# eib-128.net
KiCad netlist of a schematic drawn in EAGLE
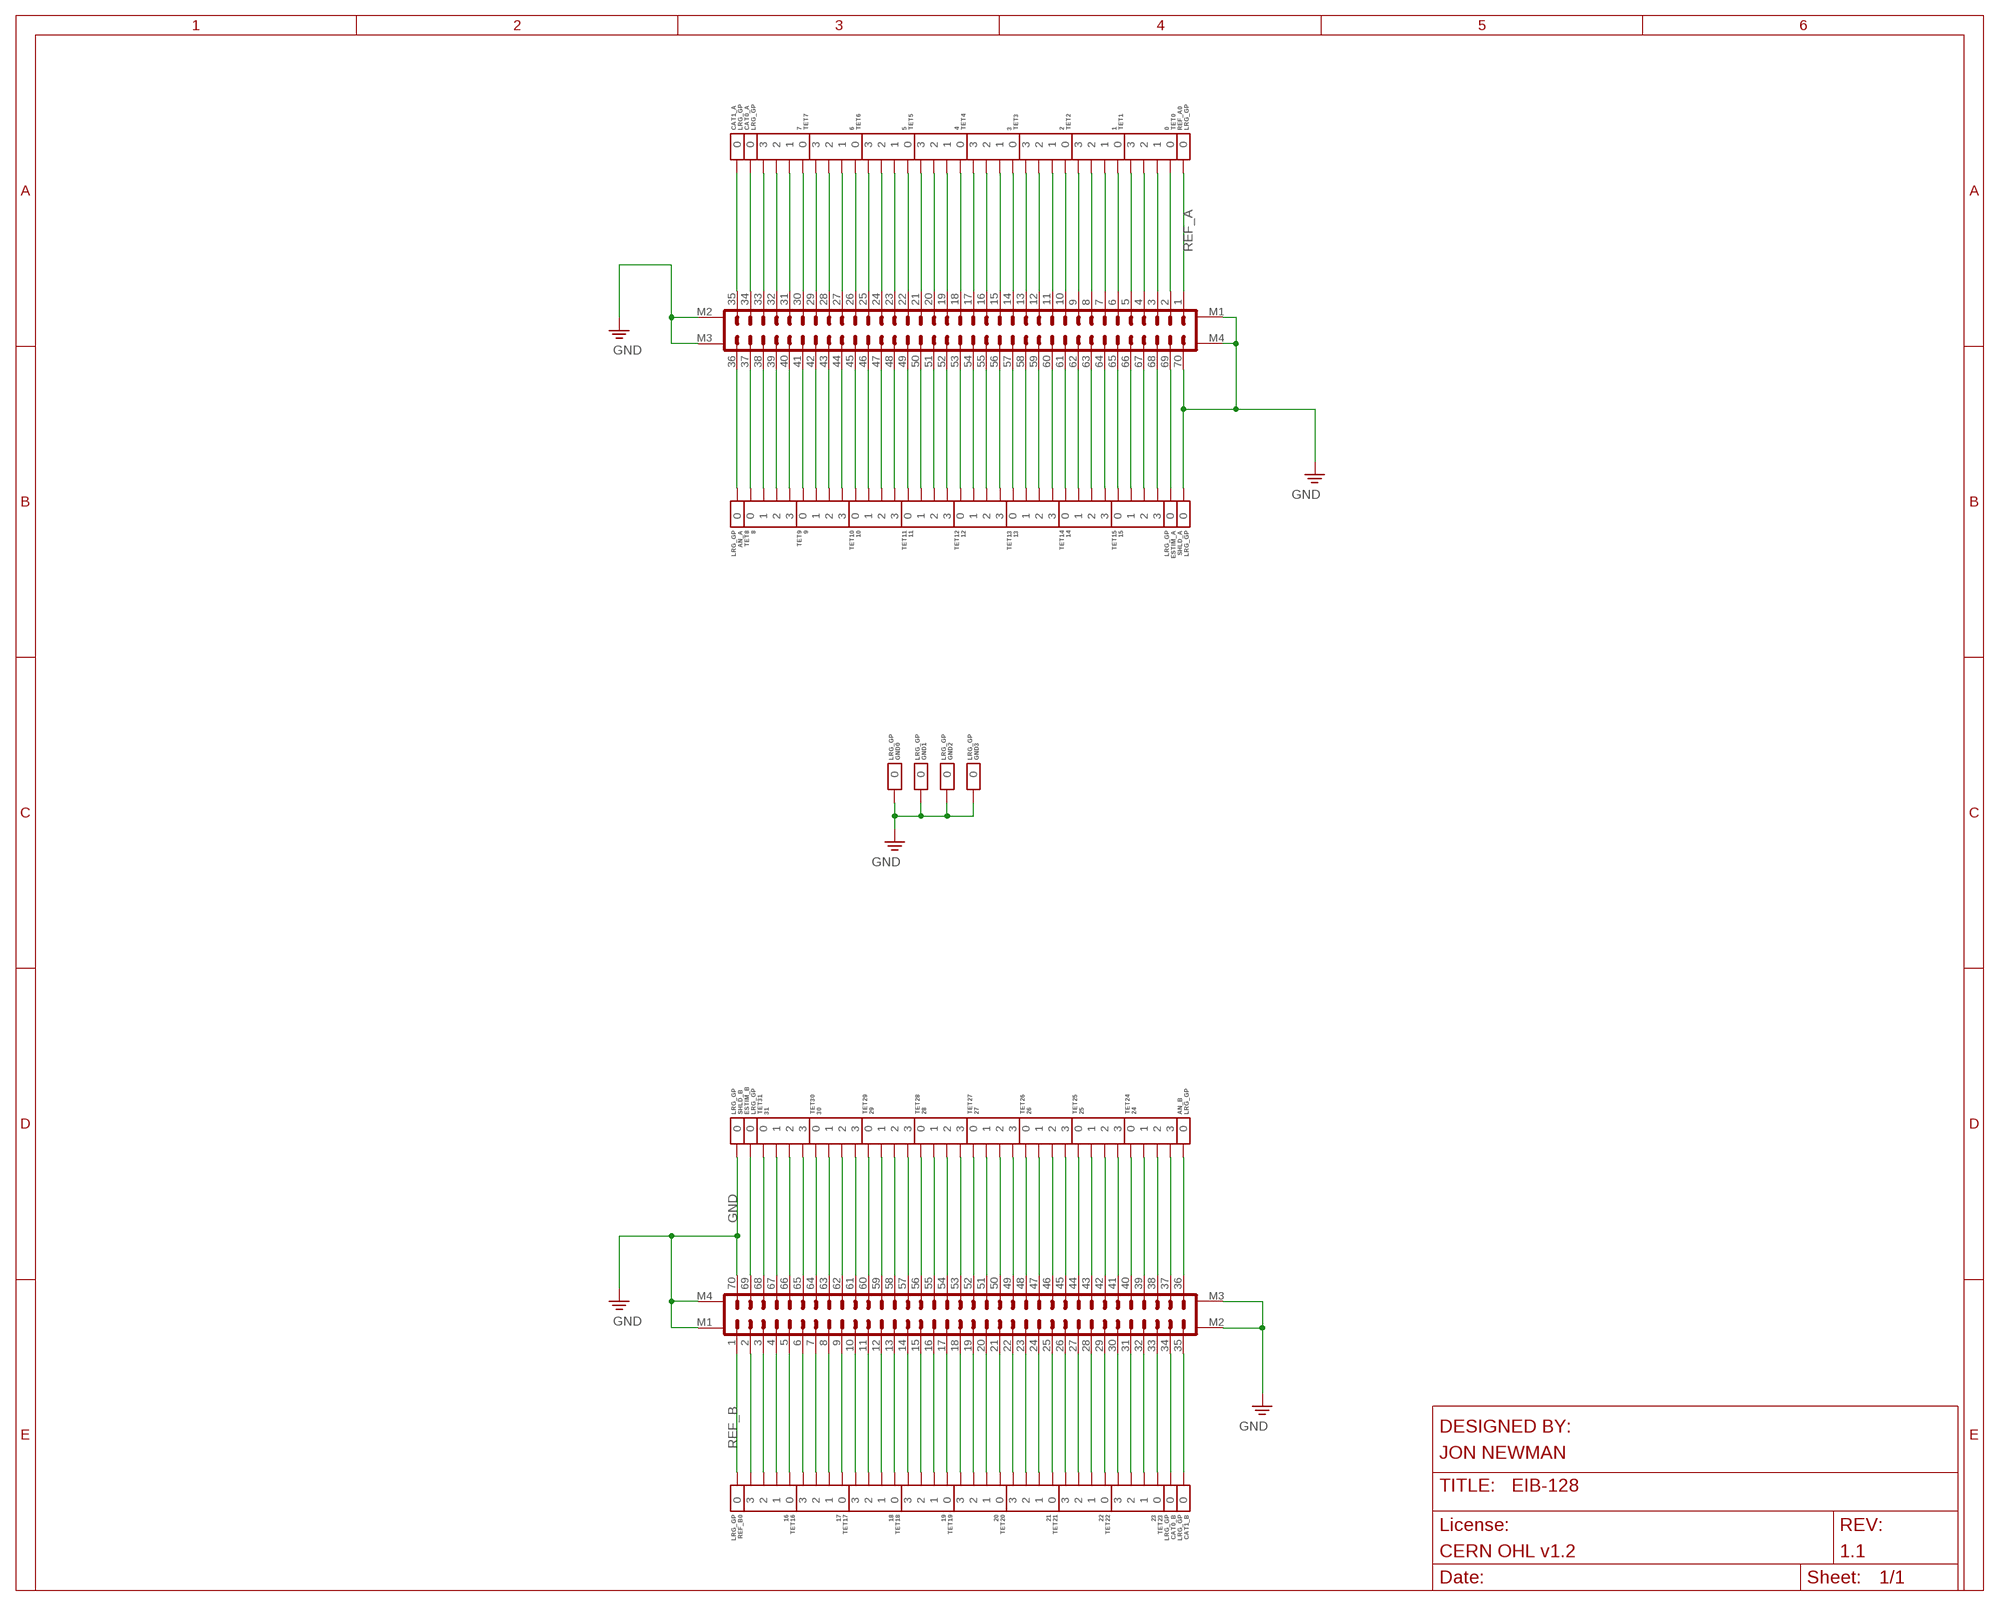
[diagram p0: schematic, sheet 1]

(export (version "E")
  (design (tool "Eeschema 10.0.6"))
  (components
    (comp (ref "A")
      (value "DF40HEAD")
      (footprint "eagle-import:DF40-70HEAD")
      (libsource (lib "eagle-import") (part "PINHD-2X35+4_DF40-70HEAD"))
    )
    (comp (ref "AN_A")
      (value "LRG_GP")
      (footprint "eagle-import:GOLDPIN_0.5ID_0.7OD")
      (libsource (lib "eagle-import") (part "GOLDPIN_0.5ID_0.7OD"))
    )
    (comp (ref "AN_B")
      (value "LRG_GP")
      (footprint "eagle-import:GOLDPIN_0.5ID_0.7OD")
      (libsource (lib "eagle-import") (part "GOLDPIN_0.5ID_0.7OD"))
    )
    (comp (ref "B")
      (value "DF40HEAD")
      (footprint "eagle-import:DF40-70HEAD")
      (libsource (lib "eagle-import") (part "PINHD-2X35+4_DF40-70HEAD"))
    )
    (comp (ref "CAT0_A")
      (value "LRG_GP")
      (footprint "eagle-import:GOLDPIN_0.5ID_0.7OD")
      (libsource (lib "eagle-import") (part "GOLDPIN_0.5ID_0.7OD"))
    )
    (comp (ref "CAT0_B")
      (value "LRG_GP")
      (footprint "eagle-import:GOLDPIN_0.5ID_0.7OD")
      (libsource (lib "eagle-import") (part "GOLDPIN_0.5ID_0.7OD"))
    )
    (comp (ref "CAT1_A")
      (value "LRG_GP")
      (footprint "eagle-import:GOLDPIN_0.5ID_0.7OD")
      (libsource (lib "eagle-import") (part "GOLDPIN_0.5ID_0.7OD"))
    )
    (comp (ref "CAT1_B")
      (value "LRG_GP")
      (footprint "eagle-import:GOLDPIN_0.5ID_0.7OD")
      (libsource (lib "eagle-import") (part "GOLDPIN_0.5ID_0.7OD"))
    )
    (comp (ref "ESTIM_A")
      (value "LRG_GP")
      (footprint "eagle-import:GOLDPIN_0.5ID_0.7OD")
      (libsource (lib "eagle-import") (part "GOLDPIN_0.5ID_0.7OD"))
    )
    (comp (ref "ESTIM_B")
      (value "LRG_GP")
      (footprint "eagle-import:GOLDPIN_0.5ID_0.7OD")
      (libsource (lib "eagle-import") (part "GOLDPIN_0.5ID_0.7OD"))
    )
    (comp (ref "GND0")
      (value "LRG_GP")
      (footprint "eagle-import:GOLDPIN_0.5ID_0.7OD")
      (libsource (lib "eagle-import") (part "GOLDPIN_0.5ID_0.7OD"))
    )
    (comp (ref "GND1")
      (value "LRG_GP")
      (footprint "eagle-import:GOLDPIN_0.5ID_0.7OD")
      (libsource (lib "eagle-import") (part "GOLDPIN_0.5ID_0.7OD"))
    )
    (comp (ref "GND2")
      (value "LRG_GP")
      (footprint "eagle-import:GOLDPIN_0.5ID_0.7OD")
      (libsource (lib "eagle-import") (part "GOLDPIN_0.5ID_0.7OD"))
    )
    (comp (ref "GND3")
      (value "LRG_GP")
      (footprint "eagle-import:GOLDPIN_0.5ID_0.7OD")
      (libsource (lib "eagle-import") (part "GOLDPIN_0.5ID_0.7OD"))
    )
    (comp (ref "REF_A0")
      (value "LRG_GP")
      (footprint "eagle-import:GOLDPIN_0.5ID_0.7OD")
      (libsource (lib "eagle-import") (part "GOLDPIN_0.5ID_0.7OD"))
    )
    (comp (ref "REF_B0")
      (value "LRG_GP")
      (footprint "eagle-import:GOLDPIN_0.5ID_0.7OD")
      (libsource (lib "eagle-import") (part "GOLDPIN_0.5ID_0.7OD"))
    )
    (comp (ref "SHLD_A")
      (value "LRG_GP")
      (footprint "eagle-import:GOLDPIN_0.5ID_0.7OD")
      (libsource (lib "eagle-import") (part "GOLDPIN_0.5ID_0.7OD"))
    )
    (comp (ref "SHLD_B")
      (value "LRG_GP")
      (footprint "eagle-import:GOLDPIN_0.5ID_0.7OD")
      (libsource (lib "eagle-import") (part "GOLDPIN_0.5ID_0.7OD"))
    )
    (comp (ref "TET0")
      (value "0")
      (footprint "eagle-import:TETRODE_128_0.5ID_0.7OD")
      (libsource (lib "eagle-import") (part "TETRODE_128_0.5ID_0.7OD"))
    )
    (comp (ref "TET1")
      (value "1")
      (footprint "eagle-import:TETRODE_128_0.5ID_0.7OD")
      (libsource (lib "eagle-import") (part "TETRODE_128_0.5ID_0.7OD"))
    )
    (comp (ref "TET2")
      (value "2")
      (footprint "eagle-import:TETRODE_128_0.5ID_0.7OD")
      (libsource (lib "eagle-import") (part "TETRODE_128_0.5ID_0.7OD"))
    )
    (comp (ref "TET3")
      (value "3")
      (footprint "eagle-import:TETRODE_128_0.5ID_0.7OD")
      (libsource (lib "eagle-import") (part "TETRODE_128_0.5ID_0.7OD"))
    )
    (comp (ref "TET4")
      (value "4")
      (footprint "eagle-import:TETRODE_128_0.5ID_0.7OD")
      (libsource (lib "eagle-import") (part "TETRODE_128_0.5ID_0.7OD"))
    )
    (comp (ref "TET5")
      (value "5")
      (footprint "eagle-import:TETRODE_128_0.5ID_0.7OD")
      (libsource (lib "eagle-import") (part "TETRODE_128_0.5ID_0.7OD"))
    )
    (comp (ref "TET6")
      (value "6")
      (footprint "eagle-import:TETRODE_128_0.5ID_0.7OD")
      (libsource (lib "eagle-import") (part "TETRODE_128_0.5ID_0.7OD"))
    )
    (comp (ref "TET7")
      (value "7")
      (footprint "eagle-import:TETRODE_128_0.5ID_0.7OD")
      (libsource (lib "eagle-import") (part "TETRODE_128_0.5ID_0.7OD"))
    )
    (comp (ref "TET8")
      (value "8")
      (footprint "eagle-import:TETRODE_128_0.5ID_0.7OD")
      (libsource (lib "eagle-import") (part "TETRODE_128_0.5ID_0.7OD"))
    )
    (comp (ref "TET9")
      (value "9")
      (footprint "eagle-import:TETRODE_128_0.5ID_0.7OD")
      (libsource (lib "eagle-import") (part "TETRODE_128_0.5ID_0.7OD"))
    )
    (comp (ref "TET10")
      (value "10")
      (footprint "eagle-import:TETRODE_128_0.5ID_0.7OD")
      (libsource (lib "eagle-import") (part "TETRODE_128_0.5ID_0.7OD"))
    )
    (comp (ref "TET11")
      (value "11")
      (footprint "eagle-import:TETRODE_128_0.5ID_0.7OD")
      (libsource (lib "eagle-import") (part "TETRODE_128_0.5ID_0.7OD"))
    )
    (comp (ref "TET12")
      (value "12")
      (footprint "eagle-import:TETRODE_128_0.5ID_0.7OD")
      (libsource (lib "eagle-import") (part "TETRODE_128_0.5ID_0.7OD"))
    )
    (comp (ref "TET13")
      (value "13")
      (footprint "eagle-import:TETRODE_128_0.5ID_0.7OD")
      (libsource (lib "eagle-import") (part "TETRODE_128_0.5ID_0.7OD"))
    )
    (comp (ref "TET14")
      (value "14")
      (footprint "eagle-import:TETRODE_128_0.5ID_0.7OD")
      (libsource (lib "eagle-import") (part "TETRODE_128_0.5ID_0.7OD"))
    )
    (comp (ref "TET15")
      (value "15")
      (footprint "eagle-import:TETRODE_128_0.5ID_0.7OD")
      (libsource (lib "eagle-import") (part "TETRODE_128_0.5ID_0.7OD"))
    )
    (comp (ref "TET16")
      (value "16")
      (footprint "eagle-import:TETRODE_128_0.5ID_0.7OD")
      (libsource (lib "eagle-import") (part "TETRODE_128_0.5ID_0.7OD"))
    )
    (comp (ref "TET17")
      (value "17")
      (footprint "eagle-import:TETRODE_128_0.5ID_0.7OD")
      (libsource (lib "eagle-import") (part "TETRODE_128_0.5ID_0.7OD"))
    )
    (comp (ref "TET18")
      (value "18")
      (footprint "eagle-import:TETRODE_128_0.5ID_0.7OD")
      (libsource (lib "eagle-import") (part "TETRODE_128_0.5ID_0.7OD"))
    )
    (comp (ref "TET19")
      (value "19")
      (footprint "eagle-import:TETRODE_128_0.5ID_0.7OD")
      (libsource (lib "eagle-import") (part "TETRODE_128_0.5ID_0.7OD"))
    )
    (comp (ref "TET20")
      (value "20")
      (footprint "eagle-import:TETRODE_128_0.5ID_0.7OD")
      (libsource (lib "eagle-import") (part "TETRODE_128_0.5ID_0.7OD"))
    )
    (comp (ref "TET21")
      (value "21")
      (footprint "eagle-import:TETRODE_128_0.5ID_0.7OD")
      (libsource (lib "eagle-import") (part "TETRODE_128_0.5ID_0.7OD"))
    )
    (comp (ref "TET22")
      (value "22")
      (footprint "eagle-import:TETRODE_128_0.5ID_0.7OD")
      (libsource (lib "eagle-import") (part "TETRODE_128_0.5ID_0.7OD"))
    )
    (comp (ref "TET23")
      (value "23")
      (footprint "eagle-import:TETRODE_128_0.5ID_0.7OD")
      (libsource (lib "eagle-import") (part "TETRODE_128_0.5ID_0.7OD"))
    )
    (comp (ref "TET24")
      (value "24")
      (footprint "eagle-import:TETRODE_128_0.5ID_0.7OD")
      (libsource (lib "eagle-import") (part "TETRODE_128_0.5ID_0.7OD"))
    )
    (comp (ref "TET25")
      (value "25")
      (footprint "eagle-import:TETRODE_128_0.5ID_0.7OD")
      (libsource (lib "eagle-import") (part "TETRODE_128_0.5ID_0.7OD"))
    )
    (comp (ref "TET26")
      (value "26")
      (footprint "eagle-import:TETRODE_128_0.5ID_0.7OD")
      (libsource (lib "eagle-import") (part "TETRODE_128_0.5ID_0.7OD"))
    )
    (comp (ref "TET27")
      (value "27")
      (footprint "eagle-import:TETRODE_128_0.5ID_0.7OD")
      (libsource (lib "eagle-import") (part "TETRODE_128_0.5ID_0.7OD"))
    )
    (comp (ref "TET28")
      (value "28")
      (footprint "eagle-import:TETRODE_128_0.5ID_0.7OD")
      (libsource (lib "eagle-import") (part "TETRODE_128_0.5ID_0.7OD"))
    )
    (comp (ref "TET29")
      (value "29")
      (footprint "eagle-import:TETRODE_128_0.5ID_0.7OD")
      (libsource (lib "eagle-import") (part "TETRODE_128_0.5ID_0.7OD"))
    )
    (comp (ref "TET30")
      (value "30")
      (footprint "eagle-import:TETRODE_128_0.5ID_0.7OD")
      (libsource (lib "eagle-import") (part "TETRODE_128_0.5ID_0.7OD"))
    )
    (comp (ref "TET31")
      (value "31")
      (footprint "eagle-import:TETRODE_128_0.5ID_0.7OD")
      (libsource (lib "eagle-import") (part "TETRODE_128_0.5ID_0.7OD"))
    )
  )
  (nets
    (net (code "1") (name "/REF_A") (class "Default")
      (node (ref "A") (pin "1") (pinfunction "1_1") (pintype "bidirectional"))
      (node (ref "REF_A0") (pin "P$1") (pinfunction "0_P$1") (pintype "bidirectional"))
    )
    (net (code "2") (name "/REF_B") (class "Default")
      (node (ref "B") (pin "1") (pinfunction "1_1") (pintype "bidirectional"))
      (node (ref "REF_B0") (pin "P$1") (pinfunction "0_P$1") (pintype "bidirectional"))
    )
    (net (code "3") (name "GND") (class "Default")
      (node (ref "A") (pin "70") (pinfunction "70_70") (pintype "bidirectional"))
      (node (ref "A") (pin "M1") (pinfunction "M1_M1") (pintype "bidirectional"))
      (node (ref "A") (pin "M2") (pinfunction "M2_M2") (pintype "bidirectional"))
      (node (ref "A") (pin "M3") (pinfunction "M3_M3") (pintype "bidirectional"))
      (node (ref "A") (pin "M4") (pinfunction "M4_M4") (pintype "bidirectional"))
      (node (ref "B") (pin "70") (pinfunction "70_70") (pintype "bidirectional"))
      (node (ref "B") (pin "M1") (pinfunction "M1_M1") (pintype "bidirectional"))
      (node (ref "B") (pin "M2") (pinfunction "M2_M2") (pintype "bidirectional"))
      (node (ref "B") (pin "M3") (pinfunction "M3_M3") (pintype "bidirectional"))
      (node (ref "B") (pin "M4") (pinfunction "M4_M4") (pintype "bidirectional"))
      (node (ref "GND0") (pin "P$1") (pinfunction "0_P$1") (pintype "bidirectional"))
      (node (ref "GND1") (pin "P$1") (pinfunction "0_P$1") (pintype "bidirectional"))
      (node (ref "GND2") (pin "P$1") (pinfunction "0_P$1") (pintype "bidirectional"))
      (node (ref "GND3") (pin "P$1") (pinfunction "0_P$1") (pintype "bidirectional"))
      (node (ref "SHLD_A") (pin "P$1") (pinfunction "0_P$1") (pintype "bidirectional"))
      (node (ref "SHLD_B") (pin "P$1") (pinfunction "0_P$1") (pintype "bidirectional"))
    )
    (net (code "4") (name "Net-(A-Pad2)") (class "Default")
      (node (ref "A") (pin "2") (pinfunction "2_2") (pintype "bidirectional"))
      (node (ref "TET0") (pin "0") (pinfunction "0_0") (pintype "bidirectional"))
    )
    (net (code "5") (name "Net-(A-Pad3)") (class "Default")
      (node (ref "A") (pin "3") (pinfunction "3_3") (pintype "bidirectional"))
      (node (ref "TET0") (pin "1") (pinfunction "1_1") (pintype "bidirectional"))
    )
    (net (code "6") (name "Net-(A-Pad4)") (class "Default")
      (node (ref "A") (pin "4") (pinfunction "4_4") (pintype "bidirectional"))
      (node (ref "TET0") (pin "2") (pinfunction "2_2") (pintype "bidirectional"))
    )
    (net (code "7") (name "Net-(A-Pad5)") (class "Default")
      (node (ref "A") (pin "5") (pinfunction "5_5") (pintype "bidirectional"))
      (node (ref "TET0") (pin "3") (pinfunction "3_3") (pintype "bidirectional"))
    )
    (net (code "8") (name "Net-(A-Pad6)") (class "Default")
      (node (ref "A") (pin "6") (pinfunction "6_6") (pintype "bidirectional"))
      (node (ref "TET1") (pin "0") (pinfunction "0_0") (pintype "bidirectional"))
    )
    (net (code "9") (name "Net-(A-Pad7)") (class "Default")
      (node (ref "A") (pin "7") (pinfunction "7_7") (pintype "bidirectional"))
      (node (ref "TET1") (pin "1") (pinfunction "1_1") (pintype "bidirectional"))
    )
    (net (code "10") (name "Net-(A-Pad8)") (class "Default")
      (node (ref "A") (pin "8") (pinfunction "8_8") (pintype "bidirectional"))
      (node (ref "TET1") (pin "2") (pinfunction "2_2") (pintype "bidirectional"))
    )
    (net (code "11") (name "Net-(A-Pad9)") (class "Default")
      (node (ref "A") (pin "9") (pinfunction "9_9") (pintype "bidirectional"))
      (node (ref "TET1") (pin "3") (pinfunction "3_3") (pintype "bidirectional"))
    )
    (net (code "12") (name "Net-(A-Pad10)") (class "Default")
      (node (ref "A") (pin "10") (pinfunction "10_10") (pintype "bidirectional"))
      (node (ref "TET2") (pin "0") (pinfunction "0_0") (pintype "bidirectional"))
    )
    (net (code "13") (name "Net-(A-Pad11)") (class "Default")
      (node (ref "A") (pin "11") (pinfunction "11_11") (pintype "bidirectional"))
      (node (ref "TET2") (pin "1") (pinfunction "1_1") (pintype "bidirectional"))
    )
    (net (code "14") (name "Net-(A-Pad12)") (class "Default")
      (node (ref "A") (pin "12") (pinfunction "12_12") (pintype "bidirectional"))
      (node (ref "TET2") (pin "2") (pinfunction "2_2") (pintype "bidirectional"))
    )
    (net (code "15") (name "Net-(A-Pad13)") (class "Default")
      (node (ref "A") (pin "13") (pinfunction "13_13") (pintype "bidirectional"))
      (node (ref "TET2") (pin "3") (pinfunction "3_3") (pintype "bidirectional"))
    )
    (net (code "16") (name "Net-(A-Pad14)") (class "Default")
      (node (ref "A") (pin "14") (pinfunction "14_14") (pintype "bidirectional"))
      (node (ref "TET3") (pin "0") (pinfunction "0_0") (pintype "bidirectional"))
    )
    (net (code "17") (name "Net-(A-Pad15)") (class "Default")
      (node (ref "A") (pin "15") (pinfunction "15_15") (pintype "bidirectional"))
      (node (ref "TET3") (pin "1") (pinfunction "1_1") (pintype "bidirectional"))
    )
    (net (code "18") (name "Net-(A-Pad16)") (class "Default")
      (node (ref "A") (pin "16") (pinfunction "16_16") (pintype "bidirectional"))
      (node (ref "TET3") (pin "2") (pinfunction "2_2") (pintype "bidirectional"))
    )
    (net (code "19") (name "Net-(A-Pad17)") (class "Default")
      (node (ref "A") (pin "17") (pinfunction "17_17") (pintype "bidirectional"))
      (node (ref "TET3") (pin "3") (pinfunction "3_3") (pintype "bidirectional"))
    )
    (net (code "20") (name "Net-(A-Pad18)") (class "Default")
      (node (ref "A") (pin "18") (pinfunction "18_18") (pintype "bidirectional"))
      (node (ref "TET4") (pin "0") (pinfunction "0_0") (pintype "bidirectional"))
    )
    (net (code "21") (name "Net-(A-Pad19)") (class "Default")
      (node (ref "A") (pin "19") (pinfunction "19_19") (pintype "bidirectional"))
      (node (ref "TET4") (pin "1") (pinfunction "1_1") (pintype "bidirectional"))
    )
    (net (code "22") (name "Net-(A-Pad20)") (class "Default")
      (node (ref "A") (pin "20") (pinfunction "20_20") (pintype "bidirectional"))
      (node (ref "TET4") (pin "2") (pinfunction "2_2") (pintype "bidirectional"))
    )
    (net (code "23") (name "Net-(A-Pad21)") (class "Default")
      (node (ref "A") (pin "21") (pinfunction "21_21") (pintype "bidirectional"))
      (node (ref "TET4") (pin "3") (pinfunction "3_3") (pintype "bidirectional"))
    )
    (net (code "24") (name "Net-(A-Pad22)") (class "Default")
      (node (ref "A") (pin "22") (pinfunction "22_22") (pintype "bidirectional"))
      (node (ref "TET5") (pin "0") (pinfunction "0_0") (pintype "bidirectional"))
    )
    (net (code "25") (name "Net-(A-Pad23)") (class "Default")
      (node (ref "A") (pin "23") (pinfunction "23_23") (pintype "bidirectional"))
      (node (ref "TET5") (pin "1") (pinfunction "1_1") (pintype "bidirectional"))
    )
    (net (code "26") (name "Net-(A-Pad24)") (class "Default")
      (node (ref "A") (pin "24") (pinfunction "24_24") (pintype "bidirectional"))
      (node (ref "TET5") (pin "2") (pinfunction "2_2") (pintype "bidirectional"))
    )
    (net (code "27") (name "Net-(A-Pad25)") (class "Default")
      (node (ref "A") (pin "25") (pinfunction "25_25") (pintype "bidirectional"))
      (node (ref "TET5") (pin "3") (pinfunction "3_3") (pintype "bidirectional"))
    )
    (net (code "28") (name "Net-(A-Pad26)") (class "Default")
      (node (ref "A") (pin "26") (pinfunction "26_26") (pintype "bidirectional"))
      (node (ref "TET6") (pin "0") (pinfunction "0_0") (pintype "bidirectional"))
    )
    (net (code "29") (name "Net-(A-Pad27)") (class "Default")
      (node (ref "A") (pin "27") (pinfunction "27_27") (pintype "bidirectional"))
      (node (ref "TET6") (pin "1") (pinfunction "1_1") (pintype "bidirectional"))
    )
    (net (code "30") (name "Net-(A-Pad28)") (class "Default")
      (node (ref "A") (pin "28") (pinfunction "28_28") (pintype "bidirectional"))
      (node (ref "TET6") (pin "2") (pinfunction "2_2") (pintype "bidirectional"))
    )
    (net (code "31") (name "Net-(A-Pad29)") (class "Default")
      (node (ref "A") (pin "29") (pinfunction "29_29") (pintype "bidirectional"))
      (node (ref "TET6") (pin "3") (pinfunction "3_3") (pintype "bidirectional"))
    )
    (net (code "32") (name "Net-(A-Pad30)") (class "Default")
      (node (ref "A") (pin "30") (pinfunction "30_30") (pintype "bidirectional"))
      (node (ref "TET7") (pin "0") (pinfunction "0_0") (pintype "bidirectional"))
    )
    (net (code "33") (name "Net-(A-Pad31)") (class "Default")
      (node (ref "A") (pin "31") (pinfunction "31_31") (pintype "bidirectional"))
      (node (ref "TET7") (pin "1") (pinfunction "1_1") (pintype "bidirectional"))
    )
    (net (code "34") (name "Net-(A-Pad32)") (class "Default")
      (node (ref "A") (pin "32") (pinfunction "32_32") (pintype "bidirectional"))
      (node (ref "TET7") (pin "2") (pinfunction "2_2") (pintype "bidirectional"))
    )
    (net (code "35") (name "Net-(A-Pad33)") (class "Default")
      (node (ref "A") (pin "33") (pinfunction "33_33") (pintype "bidirectional"))
      (node (ref "TET7") (pin "3") (pinfunction "3_3") (pintype "bidirectional"))
    )
    (net (code "36") (name "Net-(A-Pad37)") (class "Default")
      (node (ref "A") (pin "37") (pinfunction "37_37") (pintype "bidirectional"))
      (node (ref "TET8") (pin "0") (pinfunction "0_0") (pintype "bidirectional"))
    )
    (net (code "37") (name "Net-(A-Pad38)") (class "Default")
      (node (ref "A") (pin "38") (pinfunction "38_38") (pintype "bidirectional"))
      (node (ref "TET8") (pin "1") (pinfunction "1_1") (pintype "bidirectional"))
    )
    (net (code "38") (name "Net-(A-Pad39)") (class "Default")
      (node (ref "A") (pin "39") (pinfunction "39_39") (pintype "bidirectional"))
      (node (ref "TET8") (pin "2") (pinfunction "2_2") (pintype "bidirectional"))
    )
    (net (code "39") (name "Net-(A-Pad40)") (class "Default")
      (node (ref "A") (pin "40") (pinfunction "40_40") (pintype "bidirectional"))
      (node (ref "TET8") (pin "3") (pinfunction "3_3") (pintype "bidirectional"))
    )
    (net (code "40") (name "Net-(A-Pad41)") (class "Default")
      (node (ref "A") (pin "41") (pinfunction "41_41") (pintype "bidirectional"))
      (node (ref "TET9") (pin "0") (pinfunction "0_0") (pintype "bidirectional"))
    )
    (net (code "41") (name "Net-(A-Pad42)") (class "Default")
      (node (ref "A") (pin "42") (pinfunction "42_42") (pintype "bidirectional"))
      (node (ref "TET9") (pin "1") (pinfunction "1_1") (pintype "bidirectional"))
    )
    (net (code "42") (name "Net-(A-Pad43)") (class "Default")
      (node (ref "A") (pin "43") (pinfunction "43_43") (pintype "bidirectional"))
      (node (ref "TET9") (pin "2") (pinfunction "2_2") (pintype "bidirectional"))
    )
    (net (code "43") (name "Net-(A-Pad44)") (class "Default")
      (node (ref "A") (pin "44") (pinfunction "44_44") (pintype "bidirectional"))
      (node (ref "TET9") (pin "3") (pinfunction "3_3") (pintype "bidirectional"))
    )
    (net (code "44") (name "Net-(A-Pad45)") (class "Default")
      (node (ref "A") (pin "45") (pinfunction "45_45") (pintype "bidirectional"))
      (node (ref "TET10") (pin "0") (pinfunction "0_0") (pintype "bidirectional"))
    )
    (net (code "45") (name "Net-(A-Pad46)") (class "Default")
      (node (ref "A") (pin "46") (pinfunction "46_46") (pintype "bidirectional"))
      (node (ref "TET10") (pin "1") (pinfunction "1_1") (pintype "bidirectional"))
    )
    (net (code "46") (name "Net-(A-Pad47)") (class "Default")
      (node (ref "A") (pin "47") (pinfunction "47_47") (pintype "bidirectional"))
      (node (ref "TET10") (pin "2") (pinfunction "2_2") (pintype "bidirectional"))
    )
    (net (code "47") (name "Net-(A-Pad48)") (class "Default")
      (node (ref "A") (pin "48") (pinfunction "48_48") (pintype "bidirectional"))
      (node (ref "TET10") (pin "3") (pinfunction "3_3") (pintype "bidirectional"))
    )
    (net (code "48") (name "Net-(A-Pad49)") (class "Default")
      (node (ref "A") (pin "49") (pinfunction "49_49") (pintype "bidirectional"))
      (node (ref "TET11") (pin "0") (pinfunction "0_0") (pintype "bidirectional"))
    )
    (net (code "49") (name "Net-(A-Pad50)") (class "Default")
      (node (ref "A") (pin "50") (pinfunction "50_50") (pintype "bidirectional"))
      (node (ref "TET11") (pin "1") (pinfunction "1_1") (pintype "bidirectional"))
    )
    (net (code "50") (name "Net-(A-Pad51)") (class "Default")
      (node (ref "A") (pin "51") (pinfunction "51_51") (pintype "bidirectional"))
      (node (ref "TET11") (pin "2") (pinfunction "2_2") (pintype "bidirectional"))
    )
    (net (code "51") (name "Net-(A-Pad52)") (class "Default")
      (node (ref "A") (pin "52") (pinfunction "52_52") (pintype "bidirectional"))
      (node (ref "TET11") (pin "3") (pinfunction "3_3") (pintype "bidirectional"))
    )
    (net (code "52") (name "Net-(A-Pad53)") (class "Default")
      (node (ref "A") (pin "53") (pinfunction "53_53") (pintype "bidirectional"))
      (node (ref "TET12") (pin "0") (pinfunction "0_0") (pintype "bidirectional"))
    )
    (net (code "53") (name "Net-(A-Pad54)") (class "Default")
      (node (ref "A") (pin "54") (pinfunction "54_54") (pintype "bidirectional"))
      (node (ref "TET12") (pin "1") (pinfunction "1_1") (pintype "bidirectional"))
    )
    (net (code "54") (name "Net-(A-Pad55)") (class "Default")
      (node (ref "A") (pin "55") (pinfunction "55_55") (pintype "bidirectional"))
      (node (ref "TET12") (pin "2") (pinfunction "2_2") (pintype "bidirectional"))
    )
    (net (code "55") (name "Net-(A-Pad56)") (class "Default")
      (node (ref "A") (pin "56") (pinfunction "56_56") (pintype "bidirectional"))
      (node (ref "TET12") (pin "3") (pinfunction "3_3") (pintype "bidirectional"))
    )
    (net (code "56") (name "Net-(A-Pad57)") (class "Default")
      (node (ref "A") (pin "57") (pinfunction "57_57") (pintype "bidirectional"))
      (node (ref "TET13") (pin "0") (pinfunction "0_0") (pintype "bidirectional"))
    )
    (net (code "57") (name "Net-(A-Pad58)") (class "Default")
      (node (ref "A") (pin "58") (pinfunction "58_58") (pintype "bidirectional"))
      (node (ref "TET13") (pin "1") (pinfunction "1_1") (pintype "bidirectional"))
    )
    (net (code "58") (name "Net-(A-Pad59)") (class "Default")
      (node (ref "A") (pin "59") (pinfunction "59_59") (pintype "bidirectional"))
      (node (ref "TET13") (pin "2") (pinfunction "2_2") (pintype "bidirectional"))
    )
    (net (code "59") (name "Net-(A-Pad60)") (class "Default")
      (node (ref "A") (pin "60") (pinfunction "60_60") (pintype "bidirectional"))
      (node (ref "TET13") (pin "3") (pinfunction "3_3") (pintype "bidirectional"))
    )
    (net (code "60") (name "Net-(A-Pad61)") (class "Default")
      (node (ref "A") (pin "61") (pinfunction "61_61") (pintype "bidirectional"))
      (node (ref "TET14") (pin "0") (pinfunction "0_0") (pintype "bidirectional"))
    )
    (net (code "61") (name "Net-(A-Pad62)") (class "Default")
      (node (ref "A") (pin "62") (pinfunction "62_62") (pintype "bidirectional"))
      (node (ref "TET14") (pin "1") (pinfunction "1_1") (pintype "bidirectional"))
    )
    (net (code "62") (name "Net-(A-Pad63)") (class "Default")
      (node (ref "A") (pin "63") (pinfunction "63_63") (pintype "bidirectional"))
      (node (ref "TET14") (pin "2") (pinfunction "2_2") (pintype "bidirectional"))
    )
    (net (code "63") (name "Net-(A-Pad64)") (class "Default")
      (node (ref "A") (pin "64") (pinfunction "64_64") (pintype "bidirectional"))
      (node (ref "TET14") (pin "3") (pinfunction "3_3") (pintype "bidirectional"))
    )
    (net (code "64") (name "Net-(A-Pad65)") (class "Default")
      (node (ref "A") (pin "65") (pinfunction "65_65") (pintype "bidirectional"))
      (node (ref "TET15") (pin "0") (pinfunction "0_0") (pintype "bidirectional"))
    )
    (net (code "65") (name "Net-(A-Pad66)") (class "Default")
      (node (ref "A") (pin "66") (pinfunction "66_66") (pintype "bidirectional"))
      (node (ref "TET15") (pin "1") (pinfunction "1_1") (pintype "bidirectional"))
    )
    (net (code "66") (name "Net-(A-Pad67)") (class "Default")
      (node (ref "A") (pin "67") (pinfunction "67_67") (pintype "bidirectional"))
      (node (ref "TET15") (pin "2") (pinfunction "2_2") (pintype "bidirectional"))
    )
    (net (code "67") (name "Net-(A-Pad68)") (class "Default")
      (node (ref "A") (pin "68") (pinfunction "68_68") (pintype "bidirectional"))
      (node (ref "TET15") (pin "3") (pinfunction "3_3") (pintype "bidirectional"))
    )
    (net (code "68") (name "Net-(AN_A-0)") (class "Default")
      (node (ref "A") (pin "36") (pinfunction "36_36") (pintype "bidirectional"))
      (node (ref "AN_A") (pin "P$1") (pinfunction "0_P$1") (pintype "bidirectional"))
    )
    (net (code "69") (name "Net-(AN_B-0)") (class "Default")
      (node (ref "AN_B") (pin "P$1") (pinfunction "0_P$1") (pintype "bidirectional"))
      (node (ref "B") (pin "36") (pinfunction "36_36") (pintype "bidirectional"))
    )
    (net (code "70") (name "Net-(B-Pad2)") (class "Default")
      (node (ref "B") (pin "2") (pinfunction "2_2") (pintype "bidirectional"))
      (node (ref "TET16") (pin "3") (pinfunction "3_3") (pintype "bidirectional"))
    )
    (net (code "71") (name "Net-(B-Pad3)") (class "Default")
      (node (ref "B") (pin "3") (pinfunction "3_3") (pintype "bidirectional"))
      (node (ref "TET16") (pin "2") (pinfunction "2_2") (pintype "bidirectional"))
    )
    (net (code "72") (name "Net-(B-Pad4)") (class "Default")
      (node (ref "B") (pin "4") (pinfunction "4_4") (pintype "bidirectional"))
      (node (ref "TET16") (pin "1") (pinfunction "1_1") (pintype "bidirectional"))
    )
    (net (code "73") (name "Net-(B-Pad5)") (class "Default")
      (node (ref "B") (pin "5") (pinfunction "5_5") (pintype "bidirectional"))
      (node (ref "TET16") (pin "0") (pinfunction "0_0") (pintype "bidirectional"))
    )
    (net (code "74") (name "Net-(B-Pad6)") (class "Default")
      (node (ref "B") (pin "6") (pinfunction "6_6") (pintype "bidirectional"))
      (node (ref "TET17") (pin "3") (pinfunction "3_3") (pintype "bidirectional"))
    )
    (net (code "75") (name "Net-(B-Pad7)") (class "Default")
      (node (ref "B") (pin "7") (pinfunction "7_7") (pintype "bidirectional"))
      (node (ref "TET17") (pin "2") (pinfunction "2_2") (pintype "bidirectional"))
    )
    (net (code "76") (name "Net-(B-Pad8)") (class "Default")
      (node (ref "B") (pin "8") (pinfunction "8_8") (pintype "bidirectional"))
      (node (ref "TET17") (pin "1") (pinfunction "1_1") (pintype "bidirectional"))
    )
    (net (code "77") (name "Net-(B-Pad9)") (class "Default")
      (node (ref "B") (pin "9") (pinfunction "9_9") (pintype "bidirectional"))
      (node (ref "TET17") (pin "0") (pinfunction "0_0") (pintype "bidirectional"))
    )
    (net (code "78") (name "Net-(B-Pad10)") (class "Default")
      (node (ref "B") (pin "10") (pinfunction "10_10") (pintype "bidirectional"))
      (node (ref "TET18") (pin "3") (pinfunction "3_3") (pintype "bidirectional"))
    )
    (net (code "79") (name "Net-(B-Pad11)") (class "Default")
      (node (ref "B") (pin "11") (pinfunction "11_11") (pintype "bidirectional"))
      (node (ref "TET18") (pin "2") (pinfunction "2_2") (pintype "bidirectional"))
    )
    (net (code "80") (name "Net-(B-Pad12)") (class "Default")
      (node (ref "B") (pin "12") (pinfunction "12_12") (pintype "bidirectional"))
      (node (ref "TET18") (pin "1") (pinfunction "1_1") (pintype "bidirectional"))
    )
    (net (code "81") (name "Net-(B-Pad13)") (class "Default")
      (node (ref "B") (pin "13") (pinfunction "13_13") (pintype "bidirectional"))
      (node (ref "TET18") (pin "0") (pinfunction "0_0") (pintype "bidirectional"))
    )
    (net (code "82") (name "Net-(B-Pad14)") (class "Default")
      (node (ref "B") (pin "14") (pinfunction "14_14") (pintype "bidirectional"))
      (node (ref "TET19") (pin "3") (pinfunction "3_3") (pintype "bidirectional"))
    )
    (net (code "83") (name "Net-(B-Pad15)") (class "Default")
      (node (ref "B") (pin "15") (pinfunction "15_15") (pintype "bidirectional"))
      (node (ref "TET19") (pin "2") (pinfunction "2_2") (pintype "bidirectional"))
    )
    (net (code "84") (name "Net-(B-Pad16)") (class "Default")
      (node (ref "B") (pin "16") (pinfunction "16_16") (pintype "bidirectional"))
      (node (ref "TET19") (pin "1") (pinfunction "1_1") (pintype "bidirectional"))
    )
    (net (code "85") (name "Net-(B-Pad17)") (class "Default")
      (node (ref "B") (pin "17") (pinfunction "17_17") (pintype "bidirectional"))
      (node (ref "TET19") (pin "0") (pinfunction "0_0") (pintype "bidirectional"))
    )
    (net (code "86") (name "Net-(B-Pad18)") (class "Default")
      (node (ref "B") (pin "18") (pinfunction "18_18") (pintype "bidirectional"))
      (node (ref "TET20") (pin "3") (pinfunction "3_3") (pintype "bidirectional"))
    )
    (net (code "87") (name "Net-(B-Pad19)") (class "Default")
      (node (ref "B") (pin "19") (pinfunction "19_19") (pintype "bidirectional"))
      (node (ref "TET20") (pin "2") (pinfunction "2_2") (pintype "bidirectional"))
    )
    (net (code "88") (name "Net-(B-Pad20)") (class "Default")
      (node (ref "B") (pin "20") (pinfunction "20_20") (pintype "bidirectional"))
      (node (ref "TET20") (pin "1") (pinfunction "1_1") (pintype "bidirectional"))
    )
    (net (code "89") (name "Net-(B-Pad21)") (class "Default")
      (node (ref "B") (pin "21") (pinfunction "21_21") (pintype "bidirectional"))
      (node (ref "TET20") (pin "0") (pinfunction "0_0") (pintype "bidirectional"))
    )
    (net (code "90") (name "Net-(B-Pad22)") (class "Default")
      (node (ref "B") (pin "22") (pinfunction "22_22") (pintype "bidirectional"))
      (node (ref "TET21") (pin "3") (pinfunction "3_3") (pintype "bidirectional"))
    )
    (net (code "91") (name "Net-(B-Pad23)") (class "Default")
      (node (ref "B") (pin "23") (pinfunction "23_23") (pintype "bidirectional"))
      (node (ref "TET21") (pin "2") (pinfunction "2_2") (pintype "bidirectional"))
    )
    (net (code "92") (name "Net-(B-Pad24)") (class "Default")
      (node (ref "B") (pin "24") (pinfunction "24_24") (pintype "bidirectional"))
      (node (ref "TET21") (pin "1") (pinfunction "1_1") (pintype "bidirectional"))
    )
    (net (code "93") (name "Net-(B-Pad25)") (class "Default")
      (node (ref "B") (pin "25") (pinfunction "25_25") (pintype "bidirectional"))
      (node (ref "TET21") (pin "0") (pinfunction "0_0") (pintype "bidirectional"))
    )
    (net (code "94") (name "Net-(B-Pad26)") (class "Default")
      (node (ref "B") (pin "26") (pinfunction "26_26") (pintype "bidirectional"))
      (node (ref "TET22") (pin "3") (pinfunction "3_3") (pintype "bidirectional"))
    )
    (net (code "95") (name "Net-(B-Pad27)") (class "Default")
      (node (ref "B") (pin "27") (pinfunction "27_27") (pintype "bidirectional"))
      (node (ref "TET22") (pin "2") (pinfunction "2_2") (pintype "bidirectional"))
    )
    (net (code "96") (name "Net-(B-Pad28)") (class "Default")
      (node (ref "B") (pin "28") (pinfunction "28_28") (pintype "bidirectional"))
      (node (ref "TET22") (pin "1") (pinfunction "1_1") (pintype "bidirectional"))
    )
    (net (code "97") (name "Net-(B-Pad29)") (class "Default")
      (node (ref "B") (pin "29") (pinfunction "29_29") (pintype "bidirectional"))
      (node (ref "TET22") (pin "0") (pinfunction "0_0") (pintype "bidirectional"))
    )
    (net (code "98") (name "Net-(B-Pad30)") (class "Default")
      (node (ref "B") (pin "30") (pinfunction "30_30") (pintype "bidirectional"))
      (node (ref "TET23") (pin "3") (pinfunction "3_3") (pintype "bidirectional"))
    )
    (net (code "99") (name "Net-(B-Pad31)") (class "Default")
      (node (ref "B") (pin "31") (pinfunction "31_31") (pintype "bidirectional"))
      (node (ref "TET23") (pin "2") (pinfunction "2_2") (pintype "bidirectional"))
    )
    (net (code "100") (name "Net-(B-Pad32)") (class "Default")
      (node (ref "B") (pin "32") (pinfunction "32_32") (pintype "bidirectional"))
      (node (ref "TET23") (pin "1") (pinfunction "1_1") (pintype "bidirectional"))
    )
    (net (code "101") (name "Net-(B-Pad33)") (class "Default")
      (node (ref "B") (pin "33") (pinfunction "33_33") (pintype "bidirectional"))
      (node (ref "TET23") (pin "0") (pinfunction "0_0") (pintype "bidirectional"))
    )
    (net (code "102") (name "Net-(B-Pad37)") (class "Default")
      (node (ref "B") (pin "37") (pinfunction "37_37") (pintype "bidirectional"))
      (node (ref "TET24") (pin "3") (pinfunction "3_3") (pintype "bidirectional"))
    )
    (net (code "103") (name "Net-(B-Pad38)") (class "Default")
      (node (ref "B") (pin "38") (pinfunction "38_38") (pintype "bidirectional"))
      (node (ref "TET24") (pin "2") (pinfunction "2_2") (pintype "bidirectional"))
    )
    (net (code "104") (name "Net-(B-Pad39)") (class "Default")
      (node (ref "B") (pin "39") (pinfunction "39_39") (pintype "bidirectional"))
      (node (ref "TET24") (pin "1") (pinfunction "1_1") (pintype "bidirectional"))
    )
    (net (code "105") (name "Net-(B-Pad40)") (class "Default")
      (node (ref "B") (pin "40") (pinfunction "40_40") (pintype "bidirectional"))
      (node (ref "TET24") (pin "0") (pinfunction "0_0") (pintype "bidirectional"))
    )
    (net (code "106") (name "Net-(B-Pad41)") (class "Default")
      (node (ref "B") (pin "41") (pinfunction "41_41") (pintype "bidirectional"))
      (node (ref "TET25") (pin "3") (pinfunction "3_3") (pintype "bidirectional"))
    )
    (net (code "107") (name "Net-(B-Pad42)") (class "Default")
      (node (ref "B") (pin "42") (pinfunction "42_42") (pintype "bidirectional"))
      (node (ref "TET25") (pin "2") (pinfunction "2_2") (pintype "bidirectional"))
    )
    (net (code "108") (name "Net-(B-Pad43)") (class "Default")
      (node (ref "B") (pin "43") (pinfunction "43_43") (pintype "bidirectional"))
      (node (ref "TET25") (pin "1") (pinfunction "1_1") (pintype "bidirectional"))
    )
    (net (code "109") (name "Net-(B-Pad44)") (class "Default")
      (node (ref "B") (pin "44") (pinfunction "44_44") (pintype "bidirectional"))
      (node (ref "TET25") (pin "0") (pinfunction "0_0") (pintype "bidirectional"))
    )
    (net (code "110") (name "Net-(B-Pad45)") (class "Default")
      (node (ref "B") (pin "45") (pinfunction "45_45") (pintype "bidirectional"))
      (node (ref "TET26") (pin "3") (pinfunction "3_3") (pintype "bidirectional"))
    )
    (net (code "111") (name "Net-(B-Pad46)") (class "Default")
      (node (ref "B") (pin "46") (pinfunction "46_46") (pintype "bidirectional"))
      (node (ref "TET26") (pin "2") (pinfunction "2_2") (pintype "bidirectional"))
    )
    (net (code "112") (name "Net-(B-Pad47)") (class "Default")
      (node (ref "B") (pin "47") (pinfunction "47_47") (pintype "bidirectional"))
      (node (ref "TET26") (pin "1") (pinfunction "1_1") (pintype "bidirectional"))
    )
    (net (code "113") (name "Net-(B-Pad48)") (class "Default")
      (node (ref "B") (pin "48") (pinfunction "48_48") (pintype "bidirectional"))
      (node (ref "TET26") (pin "0") (pinfunction "0_0") (pintype "bidirectional"))
    )
    (net (code "114") (name "Net-(B-Pad49)") (class "Default")
      (node (ref "B") (pin "49") (pinfunction "49_49") (pintype "bidirectional"))
      (node (ref "TET27") (pin "3") (pinfunction "3_3") (pintype "bidirectional"))
    )
    (net (code "115") (name "Net-(B-Pad50)") (class "Default")
      (node (ref "B") (pin "50") (pinfunction "50_50") (pintype "bidirectional"))
      (node (ref "TET27") (pin "2") (pinfunction "2_2") (pintype "bidirectional"))
    )
    (net (code "116") (name "Net-(B-Pad51)") (class "Default")
      (node (ref "B") (pin "51") (pinfunction "51_51") (pintype "bidirectional"))
      (node (ref "TET27") (pin "1") (pinfunction "1_1") (pintype "bidirectional"))
    )
    (net (code "117") (name "Net-(B-Pad52)") (class "Default")
      (node (ref "B") (pin "52") (pinfunction "52_52") (pintype "bidirectional"))
      (node (ref "TET27") (pin "0") (pinfunction "0_0") (pintype "bidirectional"))
    )
    (net (code "118") (name "Net-(B-Pad53)") (class "Default")
      (node (ref "B") (pin "53") (pinfunction "53_53") (pintype "bidirectional"))
      (node (ref "TET28") (pin "3") (pinfunction "3_3") (pintype "bidirectional"))
    )
    (net (code "119") (name "Net-(B-Pad54)") (class "Default")
      (node (ref "B") (pin "54") (pinfunction "54_54") (pintype "bidirectional"))
      (node (ref "TET28") (pin "2") (pinfunction "2_2") (pintype "bidirectional"))
    )
    (net (code "120") (name "Net-(B-Pad55)") (class "Default")
      (node (ref "B") (pin "55") (pinfunction "55_55") (pintype "bidirectional"))
      (node (ref "TET28") (pin "1") (pinfunction "1_1") (pintype "bidirectional"))
    )
    (net (code "121") (name "Net-(B-Pad56)") (class "Default")
      (node (ref "B") (pin "56") (pinfunction "56_56") (pintype "bidirectional"))
      (node (ref "TET28") (pin "0") (pinfunction "0_0") (pintype "bidirectional"))
    )
    (net (code "122") (name "Net-(B-Pad57)") (class "Default")
      (node (ref "B") (pin "57") (pinfunction "57_57") (pintype "bidirectional"))
      (node (ref "TET29") (pin "3") (pinfunction "3_3") (pintype "bidirectional"))
    )
    (net (code "123") (name "Net-(B-Pad58)") (class "Default")
      (node (ref "B") (pin "58") (pinfunction "58_58") (pintype "bidirectional"))
      (node (ref "TET29") (pin "2") (pinfunction "2_2") (pintype "bidirectional"))
    )
    (net (code "124") (name "Net-(B-Pad59)") (class "Default")
      (node (ref "B") (pin "59") (pinfunction "59_59") (pintype "bidirectional"))
      (node (ref "TET29") (pin "1") (pinfunction "1_1") (pintype "bidirectional"))
    )
    (net (code "125") (name "Net-(B-Pad60)") (class "Default")
      (node (ref "B") (pin "60") (pinfunction "60_60") (pintype "bidirectional"))
      (node (ref "TET29") (pin "0") (pinfunction "0_0") (pintype "bidirectional"))
    )
    (net (code "126") (name "Net-(B-Pad61)") (class "Default")
      (node (ref "B") (pin "61") (pinfunction "61_61") (pintype "bidirectional"))
      (node (ref "TET30") (pin "3") (pinfunction "3_3") (pintype "bidirectional"))
    )
    (net (code "127") (name "Net-(B-Pad62)") (class "Default")
      (node (ref "B") (pin "62") (pinfunction "62_62") (pintype "bidirectional"))
      (node (ref "TET30") (pin "2") (pinfunction "2_2") (pintype "bidirectional"))
    )
    (net (code "128") (name "Net-(B-Pad63)") (class "Default")
      (node (ref "B") (pin "63") (pinfunction "63_63") (pintype "bidirectional"))
      (node (ref "TET30") (pin "1") (pinfunction "1_1") (pintype "bidirectional"))
    )
    (net (code "129") (name "Net-(B-Pad64)") (class "Default")
      (node (ref "B") (pin "64") (pinfunction "64_64") (pintype "bidirectional"))
      (node (ref "TET30") (pin "0") (pinfunction "0_0") (pintype "bidirectional"))
    )
    (net (code "130") (name "Net-(B-Pad65)") (class "Default")
      (node (ref "B") (pin "65") (pinfunction "65_65") (pintype "bidirectional"))
      (node (ref "TET31") (pin "3") (pinfunction "3_3") (pintype "bidirectional"))
    )
    (net (code "131") (name "Net-(B-Pad66)") (class "Default")
      (node (ref "B") (pin "66") (pinfunction "66_66") (pintype "bidirectional"))
      (node (ref "TET31") (pin "2") (pinfunction "2_2") (pintype "bidirectional"))
    )
    (net (code "132") (name "Net-(B-Pad67)") (class "Default")
      (node (ref "B") (pin "67") (pinfunction "67_67") (pintype "bidirectional"))
      (node (ref "TET31") (pin "1") (pinfunction "1_1") (pintype "bidirectional"))
    )
    (net (code "133") (name "Net-(B-Pad68)") (class "Default")
      (node (ref "B") (pin "68") (pinfunction "68_68") (pintype "bidirectional"))
      (node (ref "TET31") (pin "0") (pinfunction "0_0") (pintype "bidirectional"))
    )
    (net (code "134") (name "Net-(CAT0_A-0)") (class "Default")
      (node (ref "A") (pin "34") (pinfunction "34_34") (pintype "bidirectional"))
      (node (ref "CAT0_A") (pin "P$1") (pinfunction "0_P$1") (pintype "bidirectional"))
    )
    (net (code "135") (name "Net-(CAT0_B-0)") (class "Default")
      (node (ref "B") (pin "34") (pinfunction "34_34") (pintype "bidirectional"))
      (node (ref "CAT0_B") (pin "P$1") (pinfunction "0_P$1") (pintype "bidirectional"))
    )
    (net (code "136") (name "Net-(CAT1_A-0)") (class "Default")
      (node (ref "A") (pin "35") (pinfunction "35_35") (pintype "bidirectional"))
      (node (ref "CAT1_A") (pin "P$1") (pinfunction "0_P$1") (pintype "bidirectional"))
    )
    (net (code "137") (name "Net-(CAT1_B-0)") (class "Default")
      (node (ref "B") (pin "35") (pinfunction "35_35") (pintype "bidirectional"))
      (node (ref "CAT1_B") (pin "P$1") (pinfunction "0_P$1") (pintype "bidirectional"))
    )
    (net (code "138") (name "Net-(ESTIM_A-0)") (class "Default")
      (node (ref "A") (pin "69") (pinfunction "69_69") (pintype "bidirectional"))
      (node (ref "ESTIM_A") (pin "P$1") (pinfunction "0_P$1") (pintype "bidirectional"))
    )
    (net (code "139") (name "Net-(ESTIM_B-0)") (class "Default")
      (node (ref "B") (pin "69") (pinfunction "69_69") (pintype "bidirectional"))
      (node (ref "ESTIM_B") (pin "P$1") (pinfunction "0_P$1") (pintype "bidirectional"))
    )
  )
)
